# BIT4_v11b.net
KiCad netlist of a schematic drawn in EAGLE
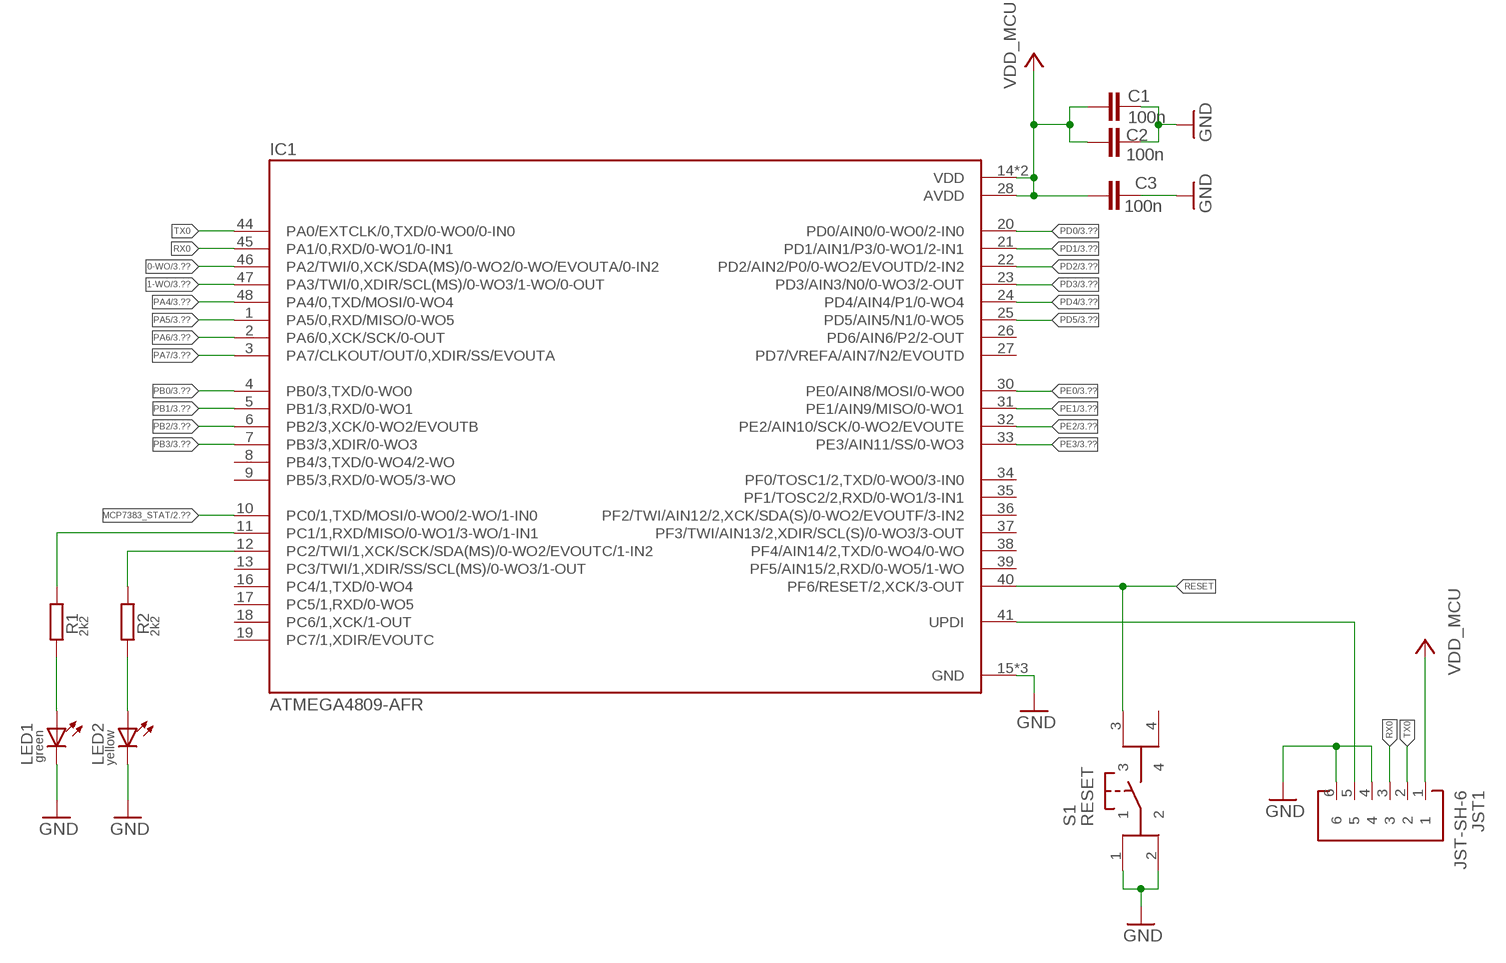
[diagram p0: schematic, sheet 1]
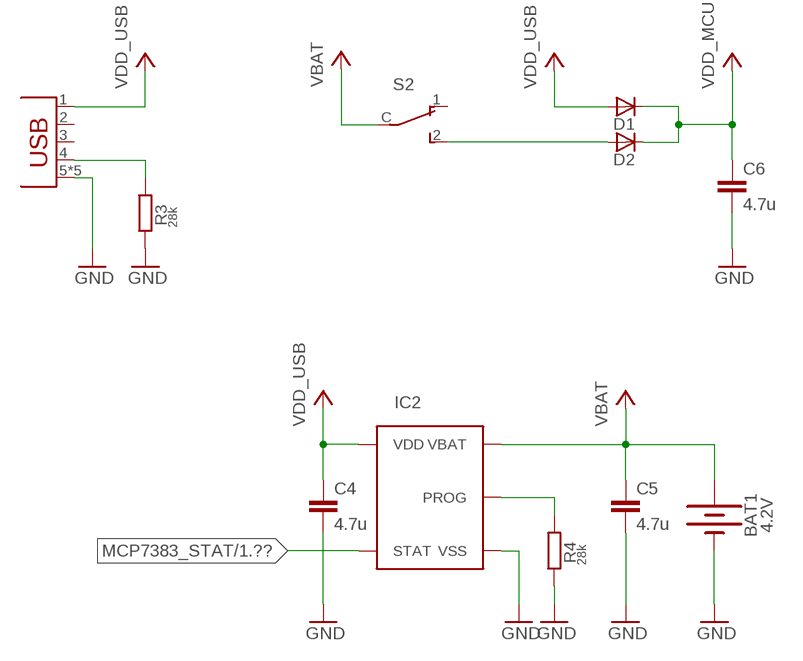
[diagram p1: schematic, sheet 2]
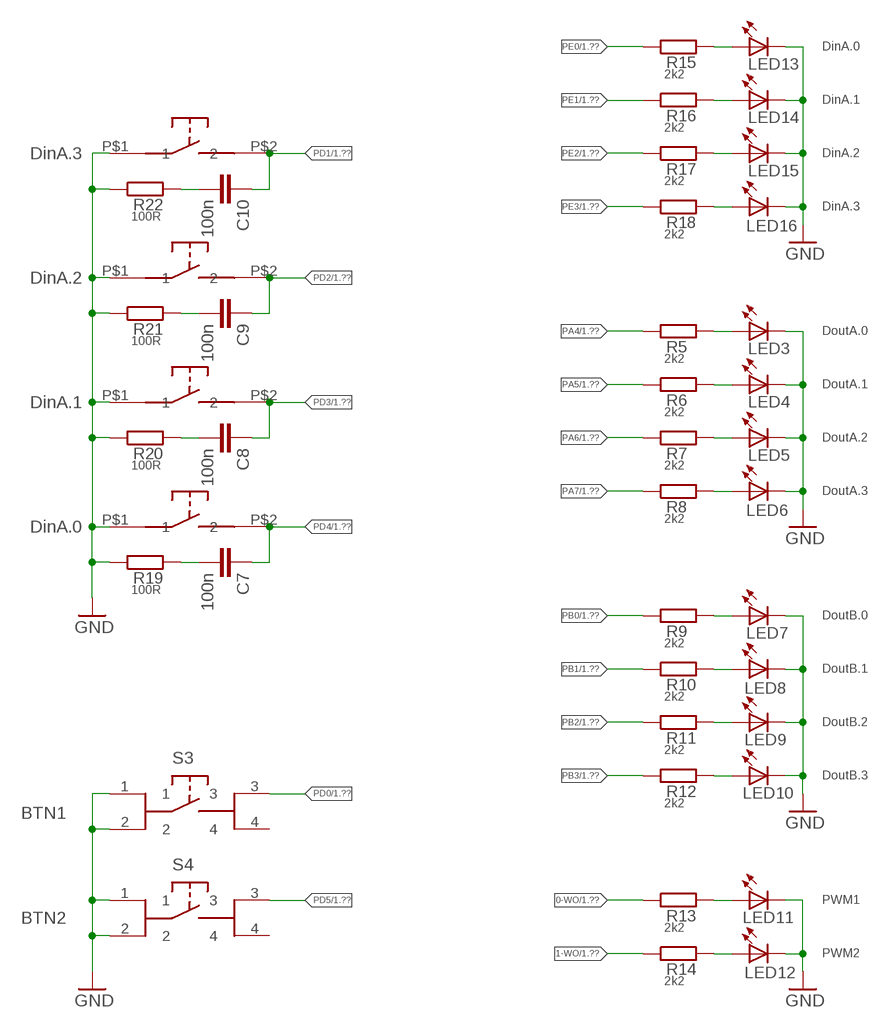
[diagram p2: schematic, sheet 3]

(export (version "E")
  (design (tool "Eeschema 10.0.6"))
  (components
    (comp (ref "C7")
      (value "100n")
      (footprint "eagle-import:C0603")
      (libsource (lib "eagle-import") (part "CAPACITORC0603"))
    )
    (comp (ref "C8")
      (value "100n")
      (footprint "eagle-import:C0603")
      (libsource (lib "eagle-import") (part "CAPACITORC0603"))
    )
    (comp (ref "C9")
      (value "100n")
      (footprint "eagle-import:C0603")
      (libsource (lib "eagle-import") (part "CAPACITORC0603"))
    )
    (comp (ref "C10")
      (value "100n")
      (footprint "eagle-import:C0603")
      (libsource (lib "eagle-import") (part "CAPACITORC0603"))
    )
    (comp (ref "LED3")
      (value "DoutA.0")
      (footprint "eagle-import:LED_1206")
      (libsource (lib "eagle-import") (part "LED"))
    )
    (comp (ref "LED4")
      (value "DoutA.1")
      (footprint "eagle-import:LED_1206")
      (libsource (lib "eagle-import") (part "LED"))
    )
    (comp (ref "LED5")
      (value "DoutA.2")
      (footprint "eagle-import:LED_1206")
      (libsource (lib "eagle-import") (part "LED"))
    )
    (comp (ref "LED6")
      (value "DoutA.3")
      (footprint "eagle-import:LED_1206")
      (libsource (lib "eagle-import") (part "LED"))
    )
    (comp (ref "LED7")
      (value "DoutB.0")
      (footprint "eagle-import:LED_1206")
      (libsource (lib "eagle-import") (part "LED"))
    )
    (comp (ref "LED8")
      (value "DoutB.1")
      (footprint "eagle-import:LED_1206")
      (libsource (lib "eagle-import") (part "LED"))
    )
    (comp (ref "LED9")
      (value "DoutB.2")
      (footprint "eagle-import:LED_1206")
      (libsource (lib "eagle-import") (part "LED"))
    )
    (comp (ref "LED10")
      (value "DoutB.3")
      (footprint "eagle-import:LED_1206")
      (libsource (lib "eagle-import") (part "LED"))
    )
    (comp (ref "LED11")
      (value "PWM1")
      (footprint "eagle-import:LED_1206")
      (libsource (lib "eagle-import") (part "LED"))
    )
    (comp (ref "LED12")
      (value "PWM2")
      (footprint "eagle-import:LED_1206")
      (libsource (lib "eagle-import") (part "LED"))
    )
    (comp (ref "LED13")
      (value "DinA.0")
      (footprint "eagle-import:LED_1206")
      (libsource (lib "eagle-import") (part "LED"))
    )
    (comp (ref "LED14")
      (value "DinA.1")
      (footprint "eagle-import:LED_1206")
      (libsource (lib "eagle-import") (part "LED"))
    )
    (comp (ref "LED15")
      (value "DinA.2")
      (footprint "eagle-import:LED_1206")
      (libsource (lib "eagle-import") (part "LED"))
    )
    (comp (ref "LED16")
      (value "DinA.3")
      (footprint "eagle-import:LED_1206")
      (libsource (lib "eagle-import") (part "LED"))
    )
    (comp (ref "R5")
      (value "2k2")
      (footprint "eagle-import:R0603")
      (libsource (lib "eagle-import") (part "RESISTOR"))
    )
    (comp (ref "R6")
      (value "2k2")
      (footprint "eagle-import:R0603")
      (libsource (lib "eagle-import") (part "RESISTOR"))
    )
    (comp (ref "R7")
      (value "2k2")
      (footprint "eagle-import:R0603")
      (libsource (lib "eagle-import") (part "RESISTOR"))
    )
    (comp (ref "R8")
      (value "2k2")
      (footprint "eagle-import:R0603")
      (libsource (lib "eagle-import") (part "RESISTOR"))
    )
    (comp (ref "R9")
      (value "2k2")
      (footprint "eagle-import:R0603")
      (libsource (lib "eagle-import") (part "RESISTOR"))
    )
    (comp (ref "R10")
      (value "2k2")
      (footprint "eagle-import:R0603")
      (libsource (lib "eagle-import") (part "RESISTOR"))
    )
    (comp (ref "R11")
      (value "2k2")
      (footprint "eagle-import:R0603")
      (libsource (lib "eagle-import") (part "RESISTOR"))
    )
    (comp (ref "R12")
      (value "2k2")
      (footprint "eagle-import:R0603")
      (libsource (lib "eagle-import") (part "RESISTOR"))
    )
    (comp (ref "R13")
      (value "2k2")
      (footprint "eagle-import:R0603")
      (libsource (lib "eagle-import") (part "RESISTOR"))
    )
    (comp (ref "R14")
      (value "2k2")
      (footprint "eagle-import:R0603")
      (libsource (lib "eagle-import") (part "RESISTOR"))
    )
    (comp (ref "R15")
      (value "2k2")
      (footprint "eagle-import:R0603")
      (libsource (lib "eagle-import") (part "RESISTOR"))
    )
    (comp (ref "R16")
      (value "2k2")
      (footprint "eagle-import:R0603")
      (libsource (lib "eagle-import") (part "RESISTOR"))
    )
    (comp (ref "R17")
      (value "2k2")
      (footprint "eagle-import:R0603")
      (libsource (lib "eagle-import") (part "RESISTOR"))
    )
    (comp (ref "R18")
      (value "2k2")
      (footprint "eagle-import:R0603")
      (libsource (lib "eagle-import") (part "RESISTOR"))
    )
    (comp (ref "R19")
      (value "100R")
      (footprint "eagle-import:R0603")
      (libsource (lib "eagle-import") (part "RESISTOR"))
    )
    (comp (ref "R20")
      (value "100R")
      (footprint "eagle-import:R0603")
      (libsource (lib "eagle-import") (part "RESISTOR"))
    )
    (comp (ref "R21")
      (value "100R")
      (footprint "eagle-import:R0603")
      (libsource (lib "eagle-import") (part "RESISTOR"))
    )
    (comp (ref "R22")
      (value "100R")
      (footprint "eagle-import:R0603")
      (libsource (lib "eagle-import") (part "RESISTOR"))
    )
    (comp (ref "S3")
      (value "BTN1")
      (footprint "eagle-import:B3FS-1012")
      (fields
        (field (name "MANUFACTURER_PART_NUMBER") "B3FS-1012")
        (field (name "RS_PART_NUMBER") "6821260P")
      )
      (libsource (lib "eagle-import") (part "BUTTON"))
    )
    (comp (ref "S4")
      (value "BTN2")
      (footprint "eagle-import:B3FS-1012")
      (fields
        (field (name "MANUFACTURER_PART_NUMBER") "B3FS-1012")
        (field (name "RS_PART_NUMBER") "6821260P")
      )
      (libsource (lib "eagle-import") (part "BUTTON"))
    )
    (comp (ref "U$1")
      (value "DinA.3")
      (footprint "eagle-import:BTN_3X6X2.5")
      (libsource (lib "eagle-import") (part "BUTTON2POL"))
    )
    (comp (ref "U$2")
      (value "DinA.2")
      (footprint "eagle-import:BTN_3X6X2.5")
      (libsource (lib "eagle-import") (part "BUTTON2POL"))
    )
    (comp (ref "U$3")
      (value "DinA.1")
      (footprint "eagle-import:BTN_3X6X2.5")
      (libsource (lib "eagle-import") (part "BUTTON2POL"))
    )
    (comp (ref "U$4")
      (value "DinA.0")
      (footprint "eagle-import:BTN_3X6X2.5")
      (libsource (lib "eagle-import") (part "BUTTON2POL"))
    )
    (comp (ref "C1")
      (value "100n")
      (footprint "eagle-import:C0603")
      (libsource (lib "eagle-import") (part "CAPACITORC0603"))
    )
    (comp (ref "C2")
      (value "100n")
      (footprint "eagle-import:C0603")
      (libsource (lib "eagle-import") (part "CAPACITORC0603"))
    )
    (comp (ref "C3")
      (value "100n")
      (footprint "eagle-import:C0603")
      (libsource (lib "eagle-import") (part "CAPACITORC0603"))
    )
    (comp (ref "IC1")
      (value "ATMEGA4809-AFR")
      (footprint "eagle-import:QFP50P900X900X120-48N")
      (fields (field (name "MF") "Microchip"))
      (libsource (lib "eagle-import") (part "ATMEGA4809-AFR"))
    )
    (comp (ref "JST1")
      (value "JST-SH-6")
      (footprint "eagle-import:JST-SH-6")
      (fields
        (field (name "MANUFACTURER_PART_NUMBER") "SM06B-SRSS-TB (LF)(SN)")
        (field (name "RS_PART_NUMBER") "5468827")
      )
      (libsource (lib "eagle-import") (part "JST-SH-6"))
    )
    (comp (ref "LED1")
      (value "green")
      (footprint "eagle-import:LED_0603")
      (libsource (lib "eagle-import") (part "LED0603"))
    )
    (comp (ref "LED2")
      (value "yellow")
      (footprint "eagle-import:LED_0603")
      (libsource (lib "eagle-import") (part "LED0603"))
    )
    (comp (ref "R1")
      (value "2k2")
      (footprint "eagle-import:R0603")
      (libsource (lib "eagle-import") (part "RESISTOR"))
    )
    (comp (ref "R2")
      (value "2k2")
      (footprint "eagle-import:R0603")
      (libsource (lib "eagle-import") (part "RESISTOR"))
    )
    (comp (ref "S1")
      (value "RESET")
      (footprint "eagle-import:B3FS-1012")
      (fields
        (field (name "MANUFACTURER_PART_NUMBER") "B3FS-1012")
        (field (name "RS_PART_NUMBER") "6821260P")
      )
      (libsource (lib "eagle-import") (part "BUTTON"))
    )
    (comp (ref "BAT1")
      (value "4.2V")
      (footprint "eagle-import:CELL-CLIP_PAD_20MM")
      (libsource (lib "eagle-import") (part "BATTERYPAD"))
    )
    (comp (ref "C4")
      (value "4.7u")
      (footprint "eagle-import:C0603")
      (libsource (lib "eagle-import") (part "CAPACITORC0603"))
    )
    (comp (ref "C5")
      (value "4.7u")
      (footprint "eagle-import:C0603")
      (libsource (lib "eagle-import") (part "CAPACITORC0603"))
    )
    (comp (ref "C6")
      (value "4.7u")
      (footprint "eagle-import:C0603")
      (libsource (lib "eagle-import") (part "CAPACITORC0603"))
    )
    (comp (ref "D1")
      (value "DIODE")
      (footprint "eagle-import:MBR0530T1")
      (libsource (lib "eagle-import") (part "DIODE"))
    )
    (comp (ref "D2")
      (value "DIODE")
      (footprint "eagle-import:MBR0530T1")
      (libsource (lib "eagle-import") (part "DIODE"))
    )
    (comp (ref "IC2")
      (value "MCP7383")
      (footprint "eagle-import:SOT23-5")
      (libsource (lib "eagle-import") (part "MCP7383"))
    )
    (comp (ref "R3")
      (value "28k")
      (footprint "eagle-import:R0603")
      (libsource (lib "eagle-import") (part "RESISTOR"))
    )
    (comp (ref "R4")
      (value "28k")
      (footprint "eagle-import:R0603")
      (libsource (lib "eagle-import") (part "RESISTOR"))
    )
    (comp (ref "S2")
      (value "SWITCH")
      (footprint "eagle-import:ESP40XX")
      (libsource (lib "eagle-import") (part "SWITCH"))
    )
    (comp (ref "USB1")
      (value "USB")
      (footprint "eagle-import:629105136821")
      (libsource (lib "eagle-import") (part "USB"))
    )
  )
  (nets
    (net (code "1") (name "0-WO") (class "Default")
      (node (ref "IC1") (pin "46") (pinfunction "PA2/TWI/0,XCK/SDA(MS)/0-WO2/0-WO/EVOUTA/0-IN2_46") (pintype "bidirectional"))
      (node (ref "R13") (pin "1") (pinfunction "1_1") (pintype "passive"))
    )
    (net (code "2") (name "1-WO") (class "Default")
      (node (ref "IC1") (pin "47") (pinfunction "PA3/TWI/0,XDIR/SCL(MS)/0-WO3/1-WO/0-OUT_47") (pintype "bidirectional"))
      (node (ref "R14") (pin "1") (pinfunction "1_1") (pintype "passive"))
    )
    (net (code "3") (name "GND") (class "Default")
      (node (ref "BAT1") (pin "-") (pinfunction "-_-") (pintype "power_in"))
      (node (ref "C1") (pin "2") (pinfunction "2_2") (pintype "passive"))
      (node (ref "C2") (pin "2") (pinfunction "2_2") (pintype "passive"))
      (node (ref "C3") (pin "2") (pinfunction "2_2") (pintype "passive"))
      (node (ref "C4") (pin "2") (pinfunction "2_2") (pintype "passive"))
      (node (ref "C5") (pin "2") (pinfunction "2_2") (pintype "passive"))
      (node (ref "C6") (pin "2") (pinfunction "2_2") (pintype "passive"))
      (node (ref "IC1") (pin "15") (pinfunction "GND_15") (pintype "power_in"))
      (node (ref "IC1") (pin "29") (pinfunction "GND_29") (pintype "power_in"))
      (node (ref "IC1") (pin "43") (pinfunction "GND_43") (pintype "power_in"))
      (node (ref "IC2") (pin "2") (pinfunction "VSS_2") (pintype "bidirectional"))
      (node (ref "JST1") (pin "4") (pinfunction "4_4") (pintype "bidirectional"))
      (node (ref "JST1") (pin "6") (pinfunction "6_6") (pintype "bidirectional"))
      (node (ref "LED1") (pin "C") (pinfunction "C_C") (pintype "passive"))
      (node (ref "LED10") (pin "C") (pinfunction "C_C") (pintype "passive"))
      (node (ref "LED11") (pin "C") (pinfunction "C_C") (pintype "passive"))
      (node (ref "LED12") (pin "C") (pinfunction "C_C") (pintype "passive"))
      (node (ref "LED13") (pin "C") (pinfunction "C_C") (pintype "passive"))
      (node (ref "LED14") (pin "C") (pinfunction "C_C") (pintype "passive"))
      (node (ref "LED15") (pin "C") (pinfunction "C_C") (pintype "passive"))
      (node (ref "LED16") (pin "C") (pinfunction "C_C") (pintype "passive"))
      (node (ref "LED2") (pin "C") (pinfunction "C_C") (pintype "passive"))
      (node (ref "LED3") (pin "C") (pinfunction "C_C") (pintype "passive"))
      (node (ref "LED4") (pin "C") (pinfunction "C_C") (pintype "passive"))
      (node (ref "LED5") (pin "C") (pinfunction "C_C") (pintype "passive"))
      (node (ref "LED6") (pin "C") (pinfunction "C_C") (pintype "passive"))
      (node (ref "LED7") (pin "C") (pinfunction "C_C") (pintype "passive"))
      (node (ref "LED8") (pin "C") (pinfunction "C_C") (pintype "passive"))
      (node (ref "LED9") (pin "C") (pinfunction "C_C") (pintype "passive"))
      (node (ref "R19") (pin "1") (pinfunction "1_1") (pintype "passive"))
      (node (ref "R20") (pin "1") (pinfunction "1_1") (pintype "passive"))
      (node (ref "R21") (pin "1") (pinfunction "1_1") (pintype "passive"))
      (node (ref "R22") (pin "1") (pinfunction "1_1") (pintype "passive"))
      (node (ref "R3") (pin "1") (pinfunction "1_1") (pintype "passive"))
      (node (ref "R4") (pin "1") (pinfunction "1_1") (pintype "passive"))
      (node (ref "S1") (pin "1") (pinfunction "1_1") (pintype "bidirectional"))
      (node (ref "S1") (pin "2") (pinfunction "2_2") (pintype "bidirectional"))
      (node (ref "S3") (pin "1") (pinfunction "1_1") (pintype "bidirectional"))
      (node (ref "S3") (pin "2") (pinfunction "2_2") (pintype "bidirectional"))
      (node (ref "S4") (pin "1") (pinfunction "1_1") (pintype "bidirectional"))
      (node (ref "S4") (pin "2") (pinfunction "2_2") (pintype "bidirectional"))
      (node (ref "U$1") (pin "P$1") (pinfunction "1_P$1") (pintype "bidirectional"))
      (node (ref "U$2") (pin "P$1") (pinfunction "1_P$1") (pintype "bidirectional"))
      (node (ref "U$3") (pin "P$1") (pinfunction "1_P$1") (pintype "bidirectional"))
      (node (ref "U$4") (pin "P$1") (pinfunction "1_P$1") (pintype "bidirectional"))
      (node (ref "USB1") (pin "5") (pinfunction "GND_5") (pintype "bidirectional"))
      (node (ref "USB1") (pin "Z1") (pinfunction "GND_Z1") (pintype "bidirectional"))
      (node (ref "USB1") (pin "Z2") (pinfunction "GND_Z2") (pintype "bidirectional"))
      (node (ref "USB1") (pin "Z3") (pinfunction "GND_Z3") (pintype "bidirectional"))
      (node (ref "USB1") (pin "Z4") (pinfunction "GND_Z4") (pintype "bidirectional"))
    )
    (net (code "4") (name "MCP7383_STAT") (class "Default")
      (node (ref "IC1") (pin "10") (pinfunction "PC0/1,TXD/MOSI/0-WO0/2-WO/1-IN0_10") (pintype "bidirectional"))
      (node (ref "IC2") (pin "1") (pinfunction "STAT_1") (pintype "bidirectional"))
    )
    (net (code "5") (name "Net-(C7-Pad2)") (class "Default")
      (node (ref "C7") (pin "2") (pinfunction "2_2") (pintype "passive"))
      (node (ref "R19") (pin "2") (pinfunction "2_2") (pintype "passive"))
    )
    (net (code "6") (name "Net-(C8-Pad2)") (class "Default")
      (node (ref "C8") (pin "2") (pinfunction "2_2") (pintype "passive"))
      (node (ref "R20") (pin "2") (pinfunction "2_2") (pintype "passive"))
    )
    (net (code "7") (name "Net-(C9-Pad2)") (class "Default")
      (node (ref "C9") (pin "2") (pinfunction "2_2") (pintype "passive"))
      (node (ref "R21") (pin "2") (pinfunction "2_2") (pintype "passive"))
    )
    (net (code "8") (name "Net-(C10-Pad2)") (class "Default")
      (node (ref "C10") (pin "2") (pinfunction "2_2") (pintype "passive"))
      (node (ref "R22") (pin "2") (pinfunction "2_2") (pintype "passive"))
    )
    (net (code "9") (name "Net-(D2-A)") (class "Default")
      (node (ref "D2") (pin "P$1") (pinfunction "A_P$1") (pintype "passive"))
      (node (ref "S2") (pin "2") (pinfunction "2_2") (pintype "passive"))
    )
    (net (code "10") (name "Net-(IC1-PC1{slash}1,RXD{slash}MISO{slash}0-WO1{slash}3-WO{slash}1-IN1)") (class "Default")
      (node (ref "IC1") (pin "11") (pinfunction "PC1/1,RXD/MISO/0-WO1/3-WO/1-IN1_11") (pintype "bidirectional"))
      (node (ref "R1") (pin "2") (pinfunction "2_2") (pintype "passive"))
    )
    (net (code "11") (name "Net-(IC1-PC2{slash}TWI{slash}1,XCK{slash}SCK{slash}SDA(MS){slash}0-WO2{slash}EVOUTC{slash}1-IN2)") (class "Default")
      (node (ref "IC1") (pin "12") (pinfunction "PC2/TWI/1,XCK/SCK/SDA(MS)/0-WO2/EVOUTC/1-IN2_12") (pintype "bidirectional"))
      (node (ref "R2") (pin "2") (pinfunction "2_2") (pintype "passive"))
    )
    (net (code "12") (name "Net-(IC1-UPDI)") (class "Default")
      (node (ref "IC1") (pin "41") (pinfunction "UPDI_41") (pintype "bidirectional"))
      (node (ref "JST1") (pin "5") (pinfunction "5_5") (pintype "bidirectional"))
    )
    (net (code "13") (name "Net-(IC2-PROG)") (class "Default")
      (node (ref "IC2") (pin "5") (pinfunction "PROG_5") (pintype "bidirectional"))
      (node (ref "R4") (pin "2") (pinfunction "2_2") (pintype "passive"))
    )
    (net (code "14") (name "Net-(LED1-PadA)") (class "Default")
      (node (ref "LED1") (pin "A") (pinfunction "A_A") (pintype "passive"))
      (node (ref "R1") (pin "1") (pinfunction "1_1") (pintype "passive"))
    )
    (net (code "15") (name "Net-(LED2-PadA)") (class "Default")
      (node (ref "LED2") (pin "A") (pinfunction "A_A") (pintype "passive"))
      (node (ref "R2") (pin "1") (pinfunction "1_1") (pintype "passive"))
    )
    (net (code "16") (name "Net-(LED3-PadA)") (class "Default")
      (node (ref "LED3") (pin "A") (pinfunction "A_A") (pintype "passive"))
      (node (ref "R5") (pin "2") (pinfunction "2_2") (pintype "passive"))
    )
    (net (code "17") (name "Net-(LED4-PadA)") (class "Default")
      (node (ref "LED4") (pin "A") (pinfunction "A_A") (pintype "passive"))
      (node (ref "R6") (pin "2") (pinfunction "2_2") (pintype "passive"))
    )
    (net (code "18") (name "Net-(LED5-PadA)") (class "Default")
      (node (ref "LED5") (pin "A") (pinfunction "A_A") (pintype "passive"))
      (node (ref "R7") (pin "2") (pinfunction "2_2") (pintype "passive"))
    )
    (net (code "19") (name "Net-(LED6-PadA)") (class "Default")
      (node (ref "LED6") (pin "A") (pinfunction "A_A") (pintype "passive"))
      (node (ref "R8") (pin "2") (pinfunction "2_2") (pintype "passive"))
    )
    (net (code "20") (name "Net-(LED7-PadA)") (class "Default")
      (node (ref "LED7") (pin "A") (pinfunction "A_A") (pintype "passive"))
      (node (ref "R9") (pin "2") (pinfunction "2_2") (pintype "passive"))
    )
    (net (code "21") (name "Net-(LED8-PadA)") (class "Default")
      (node (ref "LED8") (pin "A") (pinfunction "A_A") (pintype "passive"))
      (node (ref "R10") (pin "2") (pinfunction "2_2") (pintype "passive"))
    )
    (net (code "22") (name "Net-(LED9-PadA)") (class "Default")
      (node (ref "LED9") (pin "A") (pinfunction "A_A") (pintype "passive"))
      (node (ref "R11") (pin "2") (pinfunction "2_2") (pintype "passive"))
    )
    (net (code "23") (name "Net-(LED10-PadA)") (class "Default")
      (node (ref "LED10") (pin "A") (pinfunction "A_A") (pintype "passive"))
      (node (ref "R12") (pin "2") (pinfunction "2_2") (pintype "passive"))
    )
    (net (code "24") (name "Net-(LED11-PadA)") (class "Default")
      (node (ref "LED11") (pin "A") (pinfunction "A_A") (pintype "passive"))
      (node (ref "R13") (pin "2") (pinfunction "2_2") (pintype "passive"))
    )
    (net (code "25") (name "Net-(LED12-PadA)") (class "Default")
      (node (ref "LED12") (pin "A") (pinfunction "A_A") (pintype "passive"))
      (node (ref "R14") (pin "2") (pinfunction "2_2") (pintype "passive"))
    )
    (net (code "26") (name "Net-(LED13-PadA)") (class "Default")
      (node (ref "LED13") (pin "A") (pinfunction "A_A") (pintype "passive"))
      (node (ref "R15") (pin "2") (pinfunction "2_2") (pintype "passive"))
    )
    (net (code "27") (name "Net-(LED14-PadA)") (class "Default")
      (node (ref "LED14") (pin "A") (pinfunction "A_A") (pintype "passive"))
      (node (ref "R16") (pin "2") (pinfunction "2_2") (pintype "passive"))
    )
    (net (code "28") (name "Net-(LED15-PadA)") (class "Default")
      (node (ref "LED15") (pin "A") (pinfunction "A_A") (pintype "passive"))
      (node (ref "R17") (pin "2") (pinfunction "2_2") (pintype "passive"))
    )
    (net (code "29") (name "Net-(LED16-PadA)") (class "Default")
      (node (ref "LED16") (pin "A") (pinfunction "A_A") (pintype "passive"))
      (node (ref "R18") (pin "2") (pinfunction "2_2") (pintype "passive"))
    )
    (net (code "30") (name "Net-(USB1-USBID)") (class "Default")
      (node (ref "R3") (pin "2") (pinfunction "2_2") (pintype "passive"))
      (node (ref "USB1") (pin "4") (pinfunction "USBID_4") (pintype "bidirectional"))
    )
    (net (code "31") (name "PA4") (class "Default")
      (node (ref "IC1") (pin "48") (pinfunction "PA4/0,TXD/MOSI/0-WO4_48") (pintype "bidirectional"))
      (node (ref "R5") (pin "1") (pinfunction "1_1") (pintype "passive"))
    )
    (net (code "32") (name "PA5") (class "Default")
      (node (ref "IC1") (pin "1") (pinfunction "PA5/0,RXD/MISO/0-WO5_1") (pintype "bidirectional"))
      (node (ref "R6") (pin "1") (pinfunction "1_1") (pintype "passive"))
    )
    (net (code "33") (name "PA6") (class "Default")
      (node (ref "IC1") (pin "2") (pinfunction "PA6/0,XCK/SCK/0-OUT_2") (pintype "bidirectional"))
      (node (ref "R7") (pin "1") (pinfunction "1_1") (pintype "passive"))
    )
    (net (code "34") (name "PA7") (class "Default")
      (node (ref "IC1") (pin "3") (pinfunction "PA7/CLKOUT/OUT/0,XDIR/SS/EVOUTA_3") (pintype "bidirectional"))
      (node (ref "R8") (pin "1") (pinfunction "1_1") (pintype "passive"))
    )
    (net (code "35") (name "PB0") (class "Default")
      (node (ref "IC1") (pin "4") (pinfunction "PB0/3,TXD/0-WO0_4") (pintype "bidirectional"))
      (node (ref "R9") (pin "1") (pinfunction "1_1") (pintype "passive"))
    )
    (net (code "36") (name "PB1") (class "Default")
      (node (ref "IC1") (pin "5") (pinfunction "PB1/3,RXD/0-WO1_5") (pintype "bidirectional"))
      (node (ref "R10") (pin "1") (pinfunction "1_1") (pintype "passive"))
    )
    (net (code "37") (name "PB2") (class "Default")
      (node (ref "IC1") (pin "6") (pinfunction "PB2/3,XCK/0-WO2/EVOUTB_6") (pintype "bidirectional"))
      (node (ref "R11") (pin "1") (pinfunction "1_1") (pintype "passive"))
    )
    (net (code "38") (name "PB3") (class "Default")
      (node (ref "IC1") (pin "7") (pinfunction "PB3/3,XDIR/0-WO3_7") (pintype "bidirectional"))
      (node (ref "R12") (pin "1") (pinfunction "1_1") (pintype "passive"))
    )
    (net (code "39") (name "PD0") (class "Default")
      (node (ref "IC1") (pin "20") (pinfunction "PD0/AIN0/0-WO0/2-IN0_20") (pintype "bidirectional"))
      (node (ref "S3") (pin "3") (pinfunction "3_3") (pintype "bidirectional"))
    )
    (net (code "40") (name "PD1") (class "Default")
      (node (ref "C10") (pin "1") (pinfunction "1_1") (pintype "passive"))
      (node (ref "IC1") (pin "21") (pinfunction "PD1/AIN1/P3/0-WO1/2-IN1_21") (pintype "bidirectional"))
      (node (ref "U$1") (pin "P$2") (pinfunction "2_P$2") (pintype "bidirectional"))
    )
    (net (code "41") (name "PD2") (class "Default")
      (node (ref "C9") (pin "1") (pinfunction "1_1") (pintype "passive"))
      (node (ref "IC1") (pin "22") (pinfunction "PD2/AIN2/P0/0-WO2/EVOUTD/2-IN2_22") (pintype "bidirectional"))
      (node (ref "U$2") (pin "P$2") (pinfunction "2_P$2") (pintype "bidirectional"))
    )
    (net (code "42") (name "PD3") (class "Default")
      (node (ref "C8") (pin "1") (pinfunction "1_1") (pintype "passive"))
      (node (ref "IC1") (pin "23") (pinfunction "PD3/AIN3/N0/0-WO3/2-OUT_23") (pintype "bidirectional"))
      (node (ref "U$3") (pin "P$2") (pinfunction "2_P$2") (pintype "bidirectional"))
    )
    (net (code "43") (name "PD4") (class "Default")
      (node (ref "C7") (pin "1") (pinfunction "1_1") (pintype "passive"))
      (node (ref "IC1") (pin "24") (pinfunction "PD4/AIN4/P1/0-WO4_24") (pintype "bidirectional"))
      (node (ref "U$4") (pin "P$2") (pinfunction "2_P$2") (pintype "bidirectional"))
    )
    (net (code "44") (name "PD5") (class "Default")
      (node (ref "IC1") (pin "25") (pinfunction "PD5/AIN5/N1/0-WO5_25") (pintype "bidirectional"))
      (node (ref "S4") (pin "3") (pinfunction "3_3") (pintype "bidirectional"))
    )
    (net (code "45") (name "PE0") (class "Default")
      (node (ref "IC1") (pin "30") (pinfunction "PE0/AIN8/MOSI/0-WO0_30") (pintype "bidirectional"))
      (node (ref "R15") (pin "1") (pinfunction "1_1") (pintype "passive"))
    )
    (net (code "46") (name "PE1") (class "Default")
      (node (ref "IC1") (pin "31") (pinfunction "PE1/AIN9/MISO/0-WO1_31") (pintype "bidirectional"))
      (node (ref "R16") (pin "1") (pinfunction "1_1") (pintype "passive"))
    )
    (net (code "47") (name "PE2") (class "Default")
      (node (ref "IC1") (pin "32") (pinfunction "PE2/AIN10/SCK/0-WO2/EVOUTE_32") (pintype "bidirectional"))
      (node (ref "R17") (pin "1") (pinfunction "1_1") (pintype "passive"))
    )
    (net (code "48") (name "PE3") (class "Default")
      (node (ref "IC1") (pin "33") (pinfunction "PE3/AIN11/SS/0-WO3_33") (pintype "bidirectional"))
      (node (ref "R18") (pin "1") (pinfunction "1_1") (pintype "passive"))
    )
    (net (code "49") (name "RESET") (class "Default")
      (node (ref "IC1") (pin "40") (pinfunction "PF6/RESET/2,XCK/3-OUT_40") (pintype "bidirectional"))
      (node (ref "S1") (pin "3") (pinfunction "3_3") (pintype "bidirectional"))
    )
    (net (code "50") (name "RX0") (class "Default")
      (node (ref "IC1") (pin "45") (pinfunction "PA1/0,RXD/0-WO1/0-IN1_45") (pintype "bidirectional"))
      (node (ref "JST1") (pin "3") (pinfunction "3_3") (pintype "bidirectional"))
    )
    (net (code "51") (name "TX0") (class "Default")
      (node (ref "IC1") (pin "44") (pinfunction "PA0/EXTCLK/0,TXD/0-WO0/0-IN0_44") (pintype "bidirectional"))
      (node (ref "JST1") (pin "2") (pinfunction "2_2") (pintype "bidirectional"))
    )
    (net (code "52") (name "VBAT") (class "Default")
      (node (ref "BAT1") (pin "+1") (pinfunction "+_+1") (pintype "power_in"))
      (node (ref "BAT1") (pin "+2") (pinfunction "+_+2") (pintype "power_in"))
      (node (ref "C5") (pin "1") (pinfunction "1_1") (pintype "passive"))
      (node (ref "IC2") (pin "3") (pinfunction "VBAT_3") (pintype "bidirectional"))
      (node (ref "S2") (pin "C") (pinfunction "C_C") (pintype "passive"))
    )
    (net (code "53") (name "VDD_MCU") (class "Default")
      (node (ref "C1") (pin "1") (pinfunction "1_1") (pintype "passive"))
      (node (ref "C2") (pin "1") (pinfunction "1_1") (pintype "passive"))
      (node (ref "C3") (pin "1") (pinfunction "1_1") (pintype "passive"))
      (node (ref "C6") (pin "1") (pinfunction "1_1") (pintype "passive"))
      (node (ref "D1") (pin "P$2") (pinfunction "C_P$2") (pintype "passive"))
      (node (ref "D2") (pin "P$2") (pinfunction "C_P$2") (pintype "passive"))
      (node (ref "IC1") (pin "14") (pinfunction "VDD_14") (pintype "power_in"))
      (node (ref "IC1") (pin "28") (pinfunction "AVDD_28") (pintype "power_in"))
      (node (ref "IC1") (pin "42") (pinfunction "VDD_42") (pintype "power_in"))
      (node (ref "JST1") (pin "1") (pinfunction "1_1") (pintype "bidirectional"))
    )
    (net (code "54") (name "VDD_USB") (class "Default")
      (node (ref "C4") (pin "1") (pinfunction "1_1") (pintype "passive"))
      (node (ref "D1") (pin "P$1") (pinfunction "A_P$1") (pintype "passive"))
      (node (ref "IC2") (pin "4") (pinfunction "VDD_4") (pintype "bidirectional"))
      (node (ref "USB1") (pin "1") (pinfunction "VBUS_1") (pintype "bidirectional"))
    )
    (net (code "55") (name "unconnected-(IC1-PB4{slash}3,TXD{slash}0-WO4{slash}2-WO-Pad8)") (class "Default")
      (node (ref "IC1") (pin "8") (pinfunction "PB4/3,TXD/0-WO4/2-WO_8") (pintype "bidirectional"))
    )
    (net (code "56") (name "unconnected-(IC1-PB5{slash}3,RXD{slash}0-WO5{slash}3-WO-Pad9)") (class "Default")
      (node (ref "IC1") (pin "9") (pinfunction "PB5/3,RXD/0-WO5/3-WO_9") (pintype "bidirectional"))
    )
    (net (code "57") (name "unconnected-(IC1-PC3{slash}TWI{slash}1,XDIR{slash}SS{slash}SCL(MS){slash}0-WO3{slash}1-OUT-Pad13)") (class "Default")
      (node (ref "IC1") (pin "13") (pinfunction "PC3/TWI/1,XDIR/SS/SCL(MS)/0-WO3/1-OUT_13") (pintype "bidirectional"))
    )
    (net (code "58") (name "unconnected-(IC1-PC4{slash}1,TXD{slash}0-WO4-Pad16)") (class "Default")
      (node (ref "IC1") (pin "16") (pinfunction "PC4/1,TXD/0-WO4_16") (pintype "bidirectional"))
    )
    (net (code "59") (name "unconnected-(IC1-PC5{slash}1,RXD{slash}0-WO5-Pad17)") (class "Default")
      (node (ref "IC1") (pin "17") (pinfunction "PC5/1,RXD/0-WO5_17") (pintype "bidirectional"))
    )
    (net (code "60") (name "unconnected-(IC1-PC6{slash}1,XCK{slash}1-OUT-Pad18)") (class "Default")
      (node (ref "IC1") (pin "18") (pinfunction "PC6/1,XCK/1-OUT_18") (pintype "bidirectional"))
    )
    (net (code "61") (name "unconnected-(IC1-PC7{slash}1,XDIR{slash}EVOUTC-Pad19)") (class "Default")
      (node (ref "IC1") (pin "19") (pinfunction "PC7/1,XDIR/EVOUTC_19") (pintype "bidirectional"))
    )
    (net (code "62") (name "unconnected-(IC1-PD6{slash}AIN6{slash}P2{slash}2-OUT-Pad26)") (class "Default")
      (node (ref "IC1") (pin "26") (pinfunction "PD6/AIN6/P2/2-OUT_26") (pintype "bidirectional"))
    )
    (net (code "63") (name "unconnected-(IC1-PD7{slash}VREFA{slash}AIN7{slash}N2{slash}EVOUTD-Pad27)") (class "Default")
      (node (ref "IC1") (pin "27") (pinfunction "PD7/VREFA/AIN7/N2/EVOUTD_27") (pintype "bidirectional"))
    )
    (net (code "64") (name "unconnected-(IC1-PF0{slash}TOSC1{slash}2,TXD{slash}0-WO0{slash}3-IN0-Pad34)") (class "Default")
      (node (ref "IC1") (pin "34") (pinfunction "PF0/TOSC1/2,TXD/0-WO0/3-IN0_34") (pintype "bidirectional"))
    )
    (net (code "65") (name "unconnected-(IC1-PF1{slash}TOSC2{slash}2,RXD{slash}0-WO1{slash}3-IN1-Pad35)") (class "Default")
      (node (ref "IC1") (pin "35") (pinfunction "PF1/TOSC2/2,RXD/0-WO1/3-IN1_35") (pintype "bidirectional"))
    )
    (net (code "66") (name "unconnected-(IC1-PF2{slash}TWI{slash}AIN12{slash}2,XCK{slash}SDA(S){slash}0-WO2{slash}EVOUTF{slash}3-IN2-Pad36)") (class "Default")
      (node (ref "IC1") (pin "36") (pinfunction "PF2/TWI/AIN12/2,XCK/SDA(S)/0-WO2/EVOUTF/3-IN2_36") (pintype "bidirectional"))
    )
    (net (code "67") (name "unconnected-(IC1-PF3{slash}TWI{slash}AIN13{slash}2,XDIR{slash}SCL(S){slash}0-WO3{slash}3-OUT-Pad37)") (class "Default")
      (node (ref "IC1") (pin "37") (pinfunction "PF3/TWI/AIN13/2,XDIR/SCL(S)/0-WO3/3-OUT_37") (pintype "bidirectional"))
    )
    (net (code "68") (name "unconnected-(IC1-PF4{slash}AIN14{slash}2,TXD{slash}0-WO4{slash}0-WO-Pad38)") (class "Default")
      (node (ref "IC1") (pin "38") (pinfunction "PF4/AIN14/2,TXD/0-WO4/0-WO_38") (pintype "bidirectional"))
    )
    (net (code "69") (name "unconnected-(IC1-PF5{slash}AIN15{slash}2,RXD{slash}0-WO5{slash}1-WO-Pad39)") (class "Default")
      (node (ref "IC1") (pin "39") (pinfunction "PF5/AIN15/2,RXD/0-WO5/1-WO_39") (pintype "bidirectional"))
    )
    (net (code "70") (name "unconnected-(S1-Pad4)") (class "Default")
      (node (ref "S1") (pin "4") (pinfunction "4_4") (pintype "bidirectional"))
    )
    (net (code "71") (name "unconnected-(S2-Pad1)") (class "Default")
      (node (ref "S2") (pin "1") (pinfunction "1_1") (pintype "passive"))
    )
    (net (code "72") (name "unconnected-(S3-Pad4)") (class "Default")
      (node (ref "S3") (pin "4") (pinfunction "4_4") (pintype "bidirectional"))
    )
    (net (code "73") (name "unconnected-(S4-Pad4)") (class "Default")
      (node (ref "S4") (pin "4") (pinfunction "4_4") (pintype "bidirectional"))
    )
    (net (code "74") (name "unconnected-(USB1-D+-Pad3)") (class "Default")
      (node (ref "USB1") (pin "3") (pinfunction "D+_3") (pintype "bidirectional"))
    )
    (net (code "75") (name "unconnected-(USB1-D--Pad2)") (class "Default")
      (node (ref "USB1") (pin "2") (pinfunction "D-_2") (pintype "bidirectional"))
    )
  )
)
